# fan-host-board-v1_0.net
KiCad netlist of a schematic drawn in EAGLE
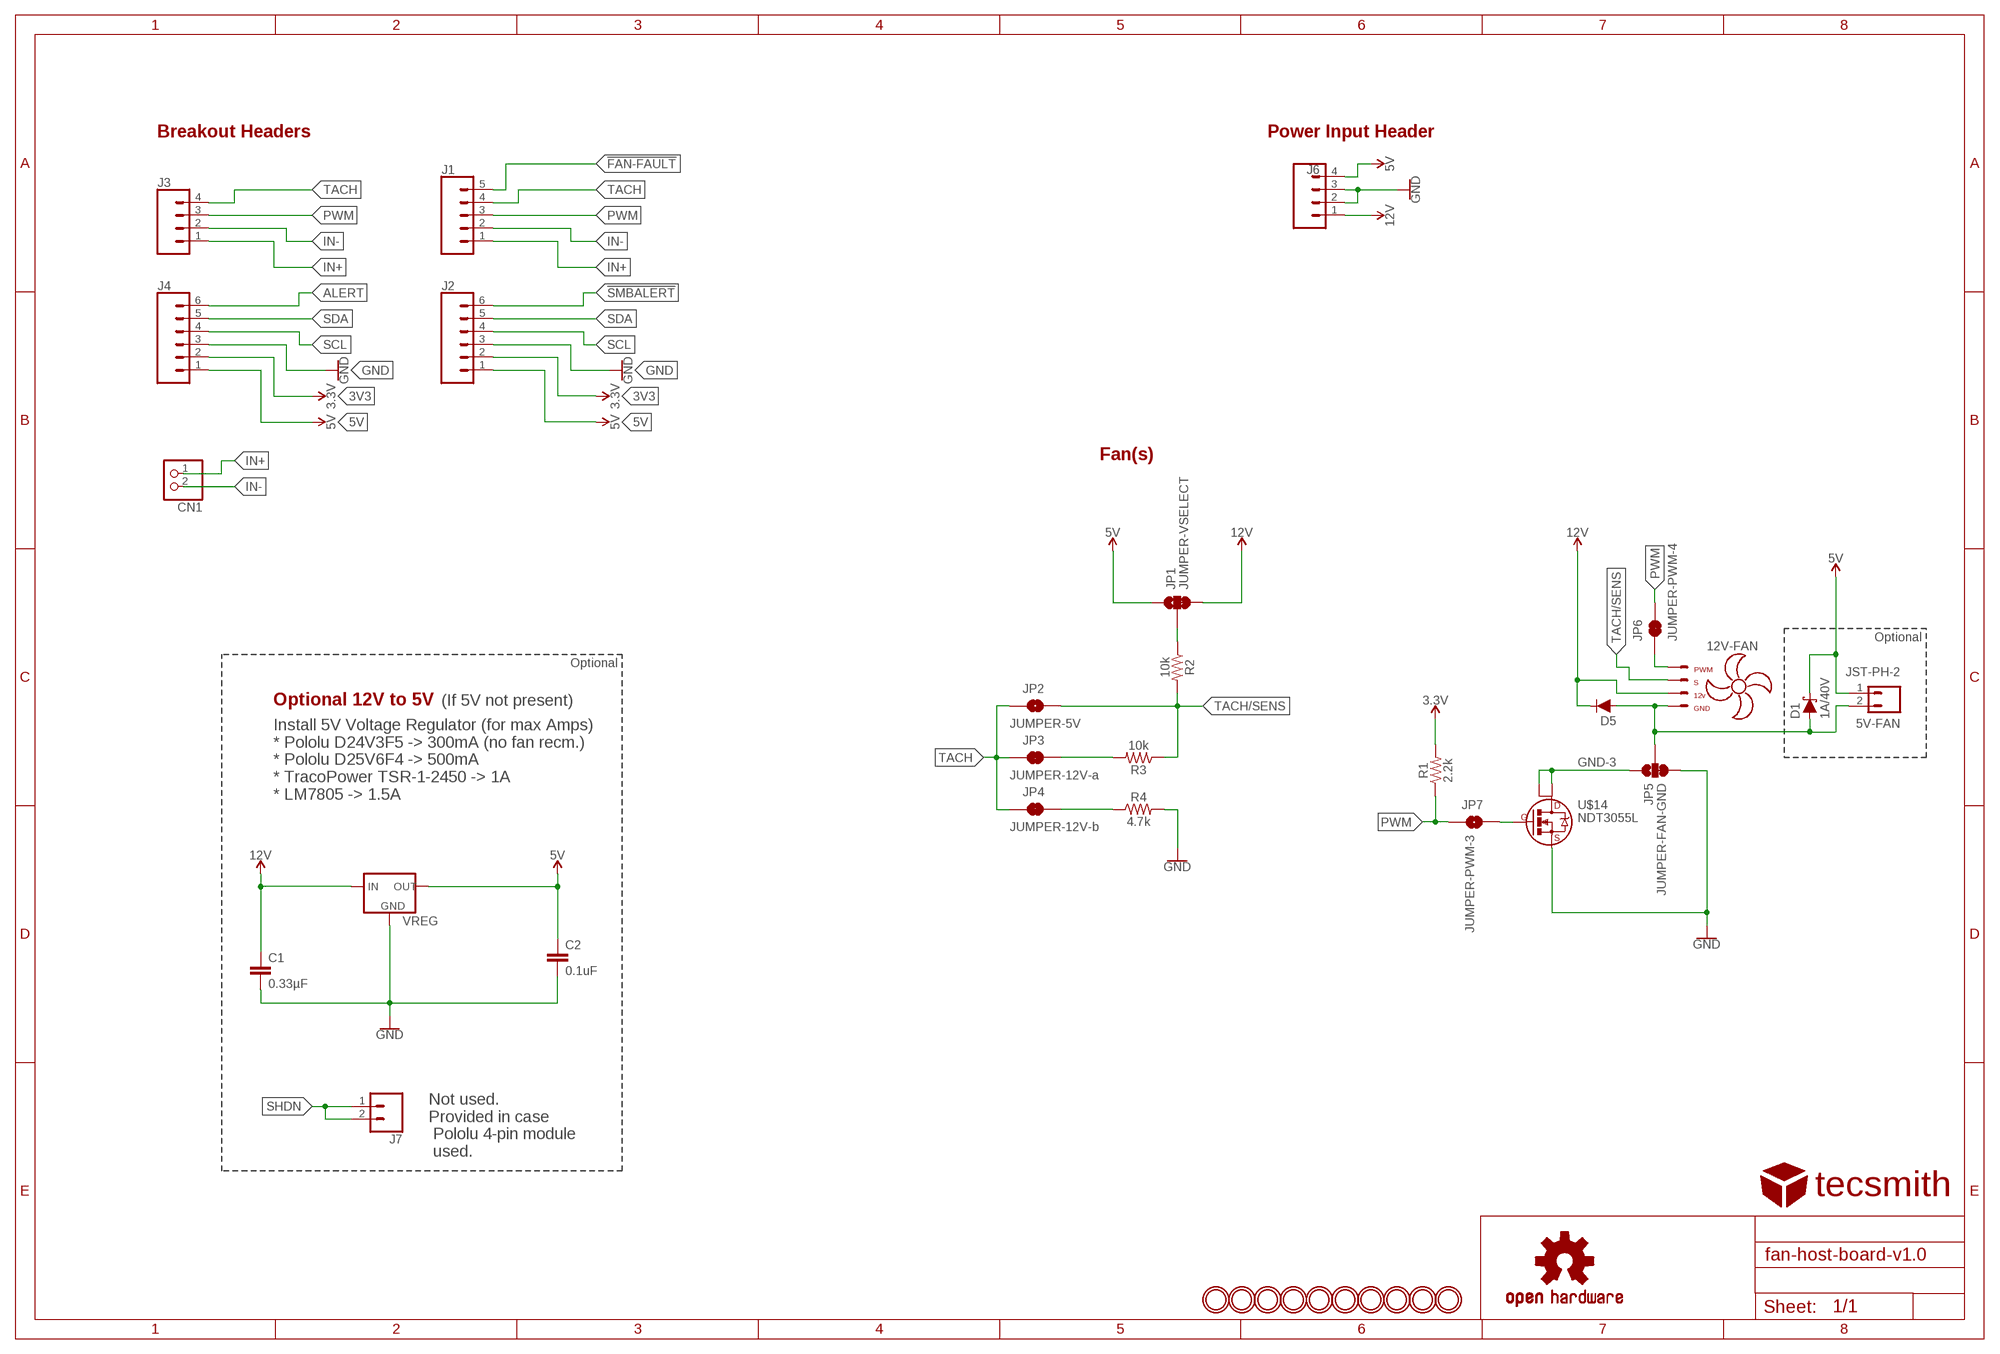
[diagram p0: schematic, sheet 1]

(export (version "E")
  (design (tool "Eeschema 10.0.6"))
  (components
    (comp (ref "5V-FAN")
      (value "JST-PH-2")
      (footprint "eagle-import:JST-PH2")
      (libsource (lib "eagle-import") (part "JST-PH-2"))
    )
    (comp (ref "12V-FAN")
      (value "KK-254-4KK-254")
      (footprint "eagle-import:MOLEX_47053-1000")
      (libsource (lib "eagle-import") (part "KK-254-4KK-254"))
    )
    (comp (ref "C1")
      (value "0.33µF")
      (footprint "eagle-import:0805")
      (libsource (lib "eagle-import") (part "0.33UF/330NF-0805-50V-10%"))
    )
    (comp (ref "C2")
      (value "0.1uF")
      (footprint "eagle-import:0603")
      (libsource (lib "eagle-import") (part "0.1UF-0603-25V-5%"))
    )
    (comp (ref "CN1")
      (value "JST_2PIN-THM")
      (footprint "eagle-import:JST-PH-2-THM")
      (libsource (lib "eagle-import") (part "JST_2PIN-THM"))
    )
    (comp (ref "D1")
      (value "1A/40V")
      (footprint "eagle-import:SMA-DIODE")
      (libsource (lib "eagle-import") (part "DIODE-SCHOTTKY-SS14"))
    )
    (comp (ref "D5")
      (value "200mA/100V")
      (footprint "eagle-import:DIODE-1N4148")
      (libsource (lib "eagle-import") (part "DIODE-1N4148"))
    )
    (comp (ref "J1")
      (value "CONN_05")
      (footprint "eagle-import:1X05")
      (libsource (lib "eagle-import") (part "CONN_05"))
    )
    (comp (ref "J2")
      (value "CONN_06SILK_FEMALE_PTH")
      (footprint "eagle-import:1X06")
      (libsource (lib "eagle-import") (part "CONN_06SILK_FEMALE_PTH"))
    )
    (comp (ref "J3")
      (value "CONN_04PTH")
      (footprint "eagle-import:1X04")
      (libsource (lib "eagle-import") (part "CONN_04PTH"))
    )
    (comp (ref "J4")
      (value "CONN_06SILK_FEMALE_PTH")
      (footprint "eagle-import:1X06")
      (libsource (lib "eagle-import") (part "CONN_06SILK_FEMALE_PTH"))
    )
    (comp (ref "J6")
      (value "CONN_04SCREW")
      (footprint "eagle-import:SCREWTERMINAL-3.5MM-4")
      (libsource (lib "eagle-import") (part "CONN_04SCREW"))
    )
    (comp (ref "J7")
      (value "CONN_021X02_NO_SILK")
      (footprint "eagle-import:1X02_NO_SILK")
      (libsource (lib "eagle-import") (part "CONN_021X02_NO_SILK"))
    )
    (comp (ref "JP1")
      (value "JUMPER-VSELECT")
      (footprint "eagle-import:SMT-JUMPER_3_1-NC_TRACE_SILK")
      (libsource (lib "eagle-import") (part "JUMPER-SMT_3_1-NC_TRACE_SILK"))
    )
    (comp (ref "JP2")
      (value "JUMPER-5V")
      (footprint "eagle-import:SMT-JUMPER_2_NO_SILK")
      (libsource (lib "eagle-import") (part "JUMPER-SMT_2_NO_NO_SILK"))
    )
    (comp (ref "JP3")
      (value "JUMPER-12V-a")
      (footprint "eagle-import:SMT-JUMPER_2_NC_TRACE_SILK")
      (libsource (lib "eagle-import") (part "JUMPER-SMT_2_NC_TRACE_SILK"))
    )
    (comp (ref "JP4")
      (value "JUMPER-12V-b")
      (footprint "eagle-import:SMT-JUMPER_2_NC_TRACE_SILK")
      (libsource (lib "eagle-import") (part "JUMPER-SMT_2_NC_TRACE_SILK"))
    )
    (comp (ref "JP5")
      (value "JUMPER-FAN-GND")
      (footprint "eagle-import:SMT-JUMPER_3_1-NC_TRACE_SILK")
      (libsource (lib "eagle-import") (part "JUMPER-SMT_3_1-NC_TRACE_SILK"))
    )
    (comp (ref "JP6")
      (value "JUMPER-PWM-4")
      (footprint "eagle-import:SMT-JUMPER_2_NC_TRACE_SILK")
      (libsource (lib "eagle-import") (part "JUMPER-SMT_2_NC_TRACE_SILK"))
    )
    (comp (ref "JP7")
      (value "JUMPER-PWM-3")
      (footprint "eagle-import:SMT-JUMPER_2_NO_SILK")
      (libsource (lib "eagle-import") (part "JUMPER-SMT_2_NO_NO_SILK"))
    )
    (comp (ref "LOGO1")
      (value "OSHW-LOGOS")
      (footprint "eagle-import:OSHW-LOGO-S")
      (libsource (lib "eagle-import") (part "OSHW-LOGOS"))
    )
    (comp (ref "R1")
      (value "2.2k")
      (footprint "eagle-import:0603")
      (libsource (lib "eagle-import") (part "2.2KOHM-0603-1/10W-1%"))
    )
    (comp (ref "R2")
      (value "10k")
      (footprint "eagle-import:0603")
      (libsource (lib "eagle-import") (part "10KOHM-0603-1/10W-1%"))
    )
    (comp (ref "R3")
      (value "10k")
      (footprint "eagle-import:0603")
      (libsource (lib "eagle-import") (part "10KOHM-0603-1/10W-1%"))
    )
    (comp (ref "R4")
      (value "4.7k")
      (footprint "eagle-import:0603")
      (libsource (lib "eagle-import") (part "4.7KOHM-0603-1/10W-1%"))
    )
    (comp (ref "U$1")
      (value "TECSMITH-LOGO")
      (footprint "eagle-import:TECSMITH-LOGO")
      (libsource (lib "eagle-import") (part "TECSMITH-LOGO"))
    )
    (comp (ref "U$3")
      (value "MOUNTINGHOLE2.5")
      (footprint "eagle-import:MOUNTINGHOLE_2.5_PLATED")
      (libsource (lib "eagle-import") (part "MOUNTINGHOLE2.5"))
    )
    (comp (ref "U$4")
      (value "MOUNTINGHOLE2.5")
      (footprint "eagle-import:MOUNTINGHOLE_2.5_PLATED")
      (libsource (lib "eagle-import") (part "MOUNTINGHOLE2.5"))
    )
    (comp (ref "U$5")
      (value "MOUNTINGHOLE2.5")
      (footprint "eagle-import:MOUNTINGHOLE_2.5_PLATED")
      (libsource (lib "eagle-import") (part "MOUNTINGHOLE2.5"))
    )
    (comp (ref "U$6")
      (value "MOUNTINGHOLE2.5")
      (footprint "eagle-import:MOUNTINGHOLE_2.5_PLATED")
      (libsource (lib "eagle-import") (part "MOUNTINGHOLE2.5"))
    )
    (comp (ref "U$7")
      (value "MOUNTINGHOLE2.5")
      (footprint "eagle-import:MOUNTINGHOLE_2.5_PLATED")
      (libsource (lib "eagle-import") (part "MOUNTINGHOLE2.5"))
    )
    (comp (ref "U$8")
      (value "MOUNTINGHOLE2.5")
      (footprint "eagle-import:MOUNTINGHOLE_2.5_PLATED")
      (libsource (lib "eagle-import") (part "MOUNTINGHOLE2.5"))
    )
    (comp (ref "U$9")
      (value "MOUNTINGHOLE2.5")
      (footprint "eagle-import:MOUNTINGHOLE_2.5_PLATED")
      (libsource (lib "eagle-import") (part "MOUNTINGHOLE2.5"))
    )
    (comp (ref "U$10")
      (value "MOUNTINGHOLE2.5")
      (footprint "eagle-import:MOUNTINGHOLE_2.5_PLATED")
      (libsource (lib "eagle-import") (part "MOUNTINGHOLE2.5"))
    )
    (comp (ref "U$11")
      (value "MOUNTINGHOLE2.5")
      (footprint "eagle-import:MOUNTINGHOLE_2.5_PLATED")
      (libsource (lib "eagle-import") (part "MOUNTINGHOLE2.5"))
    )
    (comp (ref "U$12")
      (value "MOUNTINGHOLE2.5")
      (footprint "eagle-import:MOUNTINGHOLE_2.5_PLATED")
      (libsource (lib "eagle-import") (part "MOUNTINGHOLE2.5"))
    )
    (comp (ref "U$14")
      (value "NDT3055L")
      (footprint "eagle-import:SOT223")
      (libsource (lib "eagle-import") (part "NDT3055L"))
    )
    (comp (ref "VREG")
      (value "TRACOPOWER-TSR-1")
      (footprint "eagle-import:TRACO-TSR-1")
      (libsource (lib "eagle-import") (part "TRACOPOWER-TSR-1"))
    )
  )
  (nets
    (net (code "1") (name "/GND-3") (class "Default")
      (node (ref "JP5") (pin "1") (pinfunction "1_1") (pintype "passive"))
      (node (ref "U$14") (pin "D") (pinfunction "D_D") (pintype "passive"))
      (node (ref "U$14") (pin "D2") (pinfunction "D2_D2") (pintype "passive"))
    )
    (net (code "2") (name "/~{FAN-FAULT}") (class "Default")
      (node (ref "J1") (pin "5") (pinfunction "5_5") (pintype "passive"))
    )
    (net (code "3") (name "/~{SMBALERT}") (class "Default")
      (node (ref "J2") (pin "6") (pinfunction "6_6") (pintype "passive"))
    )
    (net (code "4") (name "3V3") (class "Default")
      (node (ref "J2") (pin "2") (pinfunction "2_2") (pintype "passive"))
      (node (ref "J4") (pin "2") (pinfunction "2_2") (pintype "passive"))
      (node (ref "R1") (pin "2") (pinfunction "2_2") (pintype "passive"))
    )
    (net (code "5") (name "5V") (class "Default")
      (node (ref "5V-FAN") (pin "1") (pinfunction "1_1") (pintype "passive"))
      (node (ref "C2") (pin "1") (pinfunction "1_1") (pintype "passive"))
      (node (ref "D1") (pin "C") (pinfunction "C_C") (pintype "passive"))
      (node (ref "J2") (pin "1") (pinfunction "1_1") (pintype "passive"))
      (node (ref "J4") (pin "1") (pinfunction "1_1") (pintype "passive"))
      (node (ref "J6") (pin "4") (pinfunction "4_4") (pintype "passive"))
      (node (ref "JP1") (pin "1") (pinfunction "1_1") (pintype "passive"))
      (node (ref "VREG") (pin "P$+VOUT") (pinfunction "OUT_P$+VOUT") (pintype "output"))
    )
    (net (code "6") (name "12V") (class "Default")
      (node (ref "12V-FAN") (pin "2:+12VDC") (pinfunction "2:+12VDC_2:+12VDC") (pintype "power_in"))
      (node (ref "C1") (pin "1") (pinfunction "1_1") (pintype "passive"))
      (node (ref "D5") (pin "C") (pinfunction "C_C") (pintype "passive"))
      (node (ref "J6") (pin "1") (pinfunction "1_1") (pintype "passive"))
      (node (ref "JP1") (pin "3") (pinfunction "3_3") (pintype "passive"))
      (node (ref "VREG") (pin "P$+VIN") (pinfunction "IN_P$+VIN") (pintype "input"))
    )
    (net (code "7") (name "ALERT") (class "Default")
      (node (ref "J4") (pin "6") (pinfunction "6_6") (pintype "passive"))
    )
    (net (code "8") (name "GND") (class "Default")
      (node (ref "C1") (pin "2") (pinfunction "2_2") (pintype "passive"))
      (node (ref "C2") (pin "2") (pinfunction "2_2") (pintype "passive"))
      (node (ref "J2") (pin "3") (pinfunction "3_3") (pintype "passive"))
      (node (ref "J4") (pin "3") (pinfunction "3_3") (pintype "passive"))
      (node (ref "J6") (pin "2") (pinfunction "2_2") (pintype "passive"))
      (node (ref "J6") (pin "3") (pinfunction "3_3") (pintype "passive"))
      (node (ref "JP5") (pin "3") (pinfunction "3_3") (pintype "passive"))
      (node (ref "R4") (pin "2") (pinfunction "2_2") (pintype "passive"))
      (node (ref "U$14") (pin "S") (pinfunction "S_S") (pintype "passive"))
      (node (ref "VREG") (pin "P$GND") (pinfunction "GND_P$GND") (pintype "power_in"))
    )
    (net (code "9") (name "IN+") (class "Default")
      (node (ref "CN1") (pin "1") (pinfunction "2_1") (pintype "passive"))
      (node (ref "J1") (pin "1") (pinfunction "1_1") (pintype "passive"))
      (node (ref "J3") (pin "1") (pinfunction "1_1") (pintype "passive"))
    )
    (net (code "10") (name "IN-") (class "Default")
      (node (ref "CN1") (pin "2") (pinfunction "1_2") (pintype "passive"))
      (node (ref "J1") (pin "2") (pinfunction "2_2") (pintype "passive"))
      (node (ref "J3") (pin "2") (pinfunction "2_2") (pintype "passive"))
    )
    (net (code "11") (name "Net-(12V-FAN-Pad1:GND)") (class "Default")
      (node (ref "12V-FAN") (pin "1:GND") (pinfunction "1:GND_1:GND") (pintype "power_in"))
      (node (ref "5V-FAN") (pin "2") (pinfunction "2_2") (pintype "passive"))
      (node (ref "D1") (pin "A") (pinfunction "A_A") (pintype "passive"))
      (node (ref "D5") (pin "A") (pinfunction "A_A") (pintype "passive"))
      (node (ref "JP5") (pin "2") (pinfunction "2_2") (pintype "passive"))
    )
    (net (code "12") (name "Net-(12V-FAN-Pad4:PWM)") (class "Default")
      (node (ref "12V-FAN") (pin "4:PWM") (pinfunction "4:PWM_4:PWM") (pintype "output"))
      (node (ref "JP6") (pin "1") (pinfunction "1_1") (pintype "passive"))
    )
    (net (code "13") (name "Net-(JP1-Pad2)") (class "Default")
      (node (ref "JP1") (pin "2") (pinfunction "2_2") (pintype "passive"))
      (node (ref "R2") (pin "1") (pinfunction "1_1") (pintype "passive"))
    )
    (net (code "14") (name "Net-(JP3-Pad2)") (class "Default")
      (node (ref "JP3") (pin "2") (pinfunction "2_2") (pintype "passive"))
      (node (ref "R3") (pin "2") (pinfunction "2_2") (pintype "passive"))
    )
    (net (code "15") (name "Net-(JP4-Pad2)") (class "Default")
      (node (ref "JP4") (pin "2") (pinfunction "2_2") (pintype "passive"))
      (node (ref "R4") (pin "1") (pinfunction "1_1") (pintype "passive"))
    )
    (net (code "16") (name "Net-(JP7-Pad2)") (class "Default")
      (node (ref "JP7") (pin "2") (pinfunction "2_2") (pintype "passive"))
      (node (ref "U$14") (pin "G") (pinfunction "G_G") (pintype "passive"))
    )
    (net (code "17") (name "PWM") (class "Default")
      (node (ref "J1") (pin "3") (pinfunction "3_3") (pintype "passive"))
      (node (ref "J3") (pin "3") (pinfunction "3_3") (pintype "passive"))
      (node (ref "JP6") (pin "2") (pinfunction "2_2") (pintype "passive"))
      (node (ref "JP7") (pin "1") (pinfunction "1_1") (pintype "passive"))
      (node (ref "R1") (pin "1") (pinfunction "1_1") (pintype "passive"))
    )
    (net (code "18") (name "SCL") (class "Default")
      (node (ref "J2") (pin "4") (pinfunction "4_4") (pintype "passive"))
      (node (ref "J4") (pin "4") (pinfunction "4_4") (pintype "passive"))
    )
    (net (code "19") (name "SDA") (class "Default")
      (node (ref "J2") (pin "5") (pinfunction "5_5") (pintype "passive"))
      (node (ref "J4") (pin "5") (pinfunction "5_5") (pintype "passive"))
    )
    (net (code "20") (name "SHDN") (class "Default")
      (node (ref "J7") (pin "1") (pinfunction "1_1") (pintype "passive"))
      (node (ref "J7") (pin "2") (pinfunction "2_2") (pintype "passive"))
    )
    (net (code "21") (name "TACH") (class "Default")
      (node (ref "J1") (pin "4") (pinfunction "4_4") (pintype "passive"))
      (node (ref "J3") (pin "4") (pinfunction "4_4") (pintype "passive"))
      (node (ref "JP2") (pin "1") (pinfunction "1_1") (pintype "passive"))
      (node (ref "JP3") (pin "1") (pinfunction "1_1") (pintype "passive"))
      (node (ref "JP4") (pin "1") (pinfunction "1_1") (pintype "passive"))
    )
    (net (code "22") (name "TACH{slash}SENS") (class "Default")
      (node (ref "12V-FAN") (pin "3:TACH") (pinfunction "3:TACH_3:TACH") (pintype "input"))
      (node (ref "JP2") (pin "2") (pinfunction "2_2") (pintype "passive"))
      (node (ref "R2") (pin "2") (pinfunction "2_2") (pintype "passive"))
      (node (ref "R3") (pin "1") (pinfunction "1_1") (pintype "passive"))
    )
  )
)
